# ControlPoint.net
KiCad netlist of a schematic drawn in Altium Designer
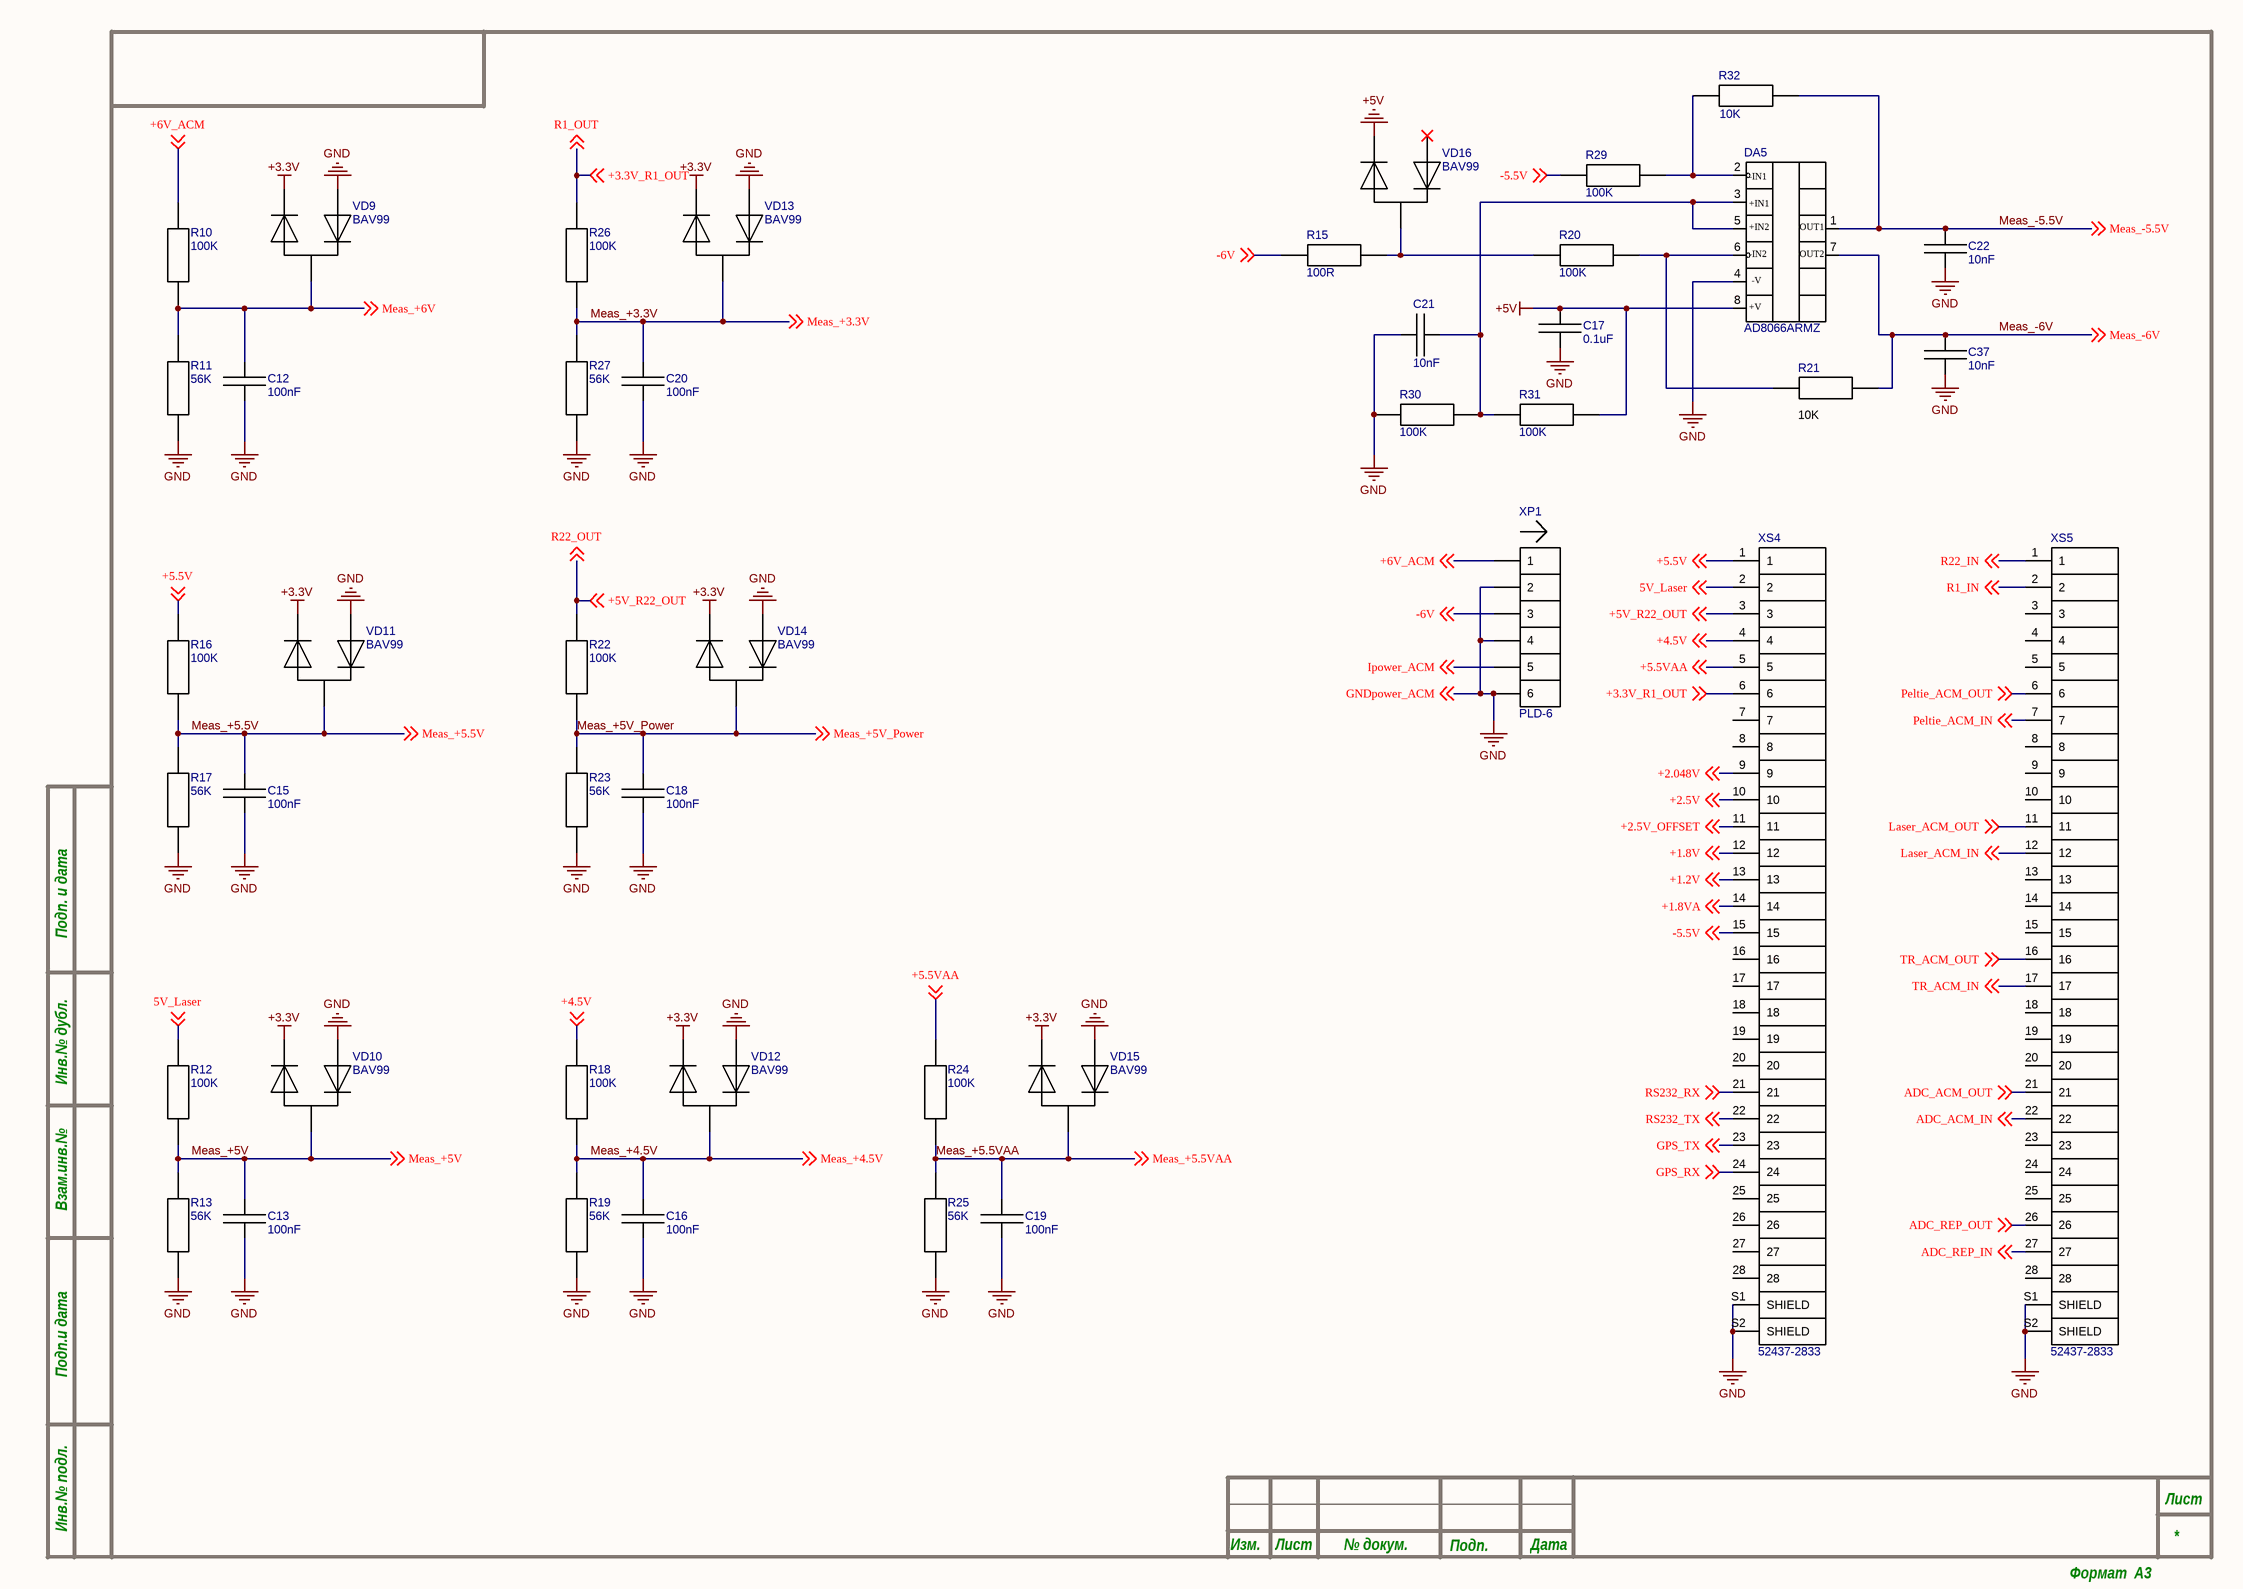
[diagram p0: ControlPoint.SchDoc]

(export (version "E")
  (design (tool "Eeschema 10.0.6"))
  (components
    (comp (ref "C12")
      (value "100nF")
      (footprint "0402C")
      (description "C0402-100nF 10% 50V")
      (fields
        (field (name "PART NUMBER") "SMD CAP CER 100nF ±10% 50V X5R 0402")
        (field (name "ADDED_BY") "Rutel@Mail.ru")
      )
      (libsource (lib "Test_Stand_Pergam") (part "C0402-100nF 10% 50V"))
    )
    (comp (ref "C13")
      (value "100nF")
      (footprint "0402C")
      (description "C0402-100nF 10% 50V")
      (fields
        (field (name "PART NUMBER") "SMD CAP CER 100nF ±10% 50V X5R 0402")
        (field (name "ADDED_BY") "Rutel@Mail.ru")
      )
      (libsource (lib "Test_Stand_Pergam") (part "C0402-100nF 10% 50V"))
    )
    (comp (ref "C15")
      (value "100nF")
      (footprint "0402C")
      (description "C0402-100nF 10% 50V")
      (fields
        (field (name "PART NUMBER") "SMD CAP CER 100nF ±10% 50V X5R 0402")
        (field (name "ADDED_BY") "Rutel@Mail.ru")
      )
      (libsource (lib "Test_Stand_Pergam") (part "C0402-100nF 10% 50V"))
    )
    (comp (ref "C16")
      (value "100nF")
      (footprint "0402C")
      (description "C0402-100nF 10% 50V")
      (fields
        (field (name "PART NUMBER") "SMD CAP CER 100nF ±10% 50V X5R 0402")
        (field (name "ADDED_BY") "Rutel@Mail.ru")
      )
      (libsource (lib "Test_Stand_Pergam") (part "C0402-100nF 10% 50V"))
    )
    (comp (ref "C17")
      (value "0.1uF")
      (footprint "0603C")
      (description "C0603 0.1UF 10% 50V")
      (fields
        (field (name "PART NUMBER") "SMD CAP CER 0.1UF ±10% 50V X7R 0603")
        (field (name "ADDED_BY") "anton@teslatec.ru")
      )
      (libsource (lib "Test_Stand_Pergam") (part "C0603-0.1UF 10% 50V"))
    )
    (comp (ref "C18")
      (value "100nF")
      (footprint "0402C")
      (description "C0402-100nF 10% 50V")
      (fields
        (field (name "PART NUMBER") "SMD CAP CER 100nF ±10% 50V X5R 0402")
        (field (name "ADDED_BY") "Rutel@Mail.ru")
      )
      (libsource (lib "Test_Stand_Pergam") (part "C0402-100nF 10% 50V"))
    )
    (comp (ref "C19")
      (value "100nF")
      (footprint "0402C")
      (description "C0402-100nF 10% 50V")
      (fields
        (field (name "PART NUMBER") "SMD CAP CER 100nF ±10% 50V X5R 0402")
        (field (name "ADDED_BY") "Rutel@Mail.ru")
      )
      (libsource (lib "Test_Stand_Pergam") (part "C0402-100nF 10% 50V"))
    )
    (comp (ref "C20")
      (value "100nF")
      (footprint "0402C")
      (description "C0402-100nF 10% 50V")
      (fields
        (field (name "PART NUMBER") "SMD CAP CER 100nF ±10% 50V X5R 0402")
        (field (name "ADDED_BY") "Rutel@Mail.ru")
      )
      (libsource (lib "Test_Stand_Pergam") (part "C0402-100nF 10% 50V"))
    )
    (comp (ref "C21")
      (value "10nF")
      (footprint "0402C")
      (description "C0402-10nF 10% 50V")
      (fields
        (field (name "PART NUMBER") "SMD CAP CER 10nF ±10% 50V X5R 0402")
        (field (name "ADDED_BY") "Rutel@Mail.ru")
      )
      (libsource (lib "Test_Stand_Pergam") (part "C0402-10nF 10% 50V"))
    )
    (comp (ref "C22")
      (value "10nF")
      (footprint "0402C")
      (description "C0402-10nF 10% 50V")
      (fields
        (field (name "PART NUMBER") "SMD CAP CER 10nF ±10% 50V X5R 0402")
        (field (name "ADDED_BY") "Rutel@Mail.ru")
      )
      (libsource (lib "Test_Stand_Pergam") (part "C0402-10nF 10% 50V"))
    )
    (comp (ref "C37")
      (value "10nF")
      (footprint "0402C")
      (description "C0402-10nF 10% 50V")
      (fields
        (field (name "PART NUMBER") "SMD CAP CER 10nF ±10% 50V X5R 0402")
        (field (name "ADDED_BY") "Rutel@Mail.ru")
      )
      (libsource (lib "Test_Stand_Pergam") (part "C0402-10nF 10% 50V"))
    )
    (comp (ref "DA5")
      (value "AD8066ARMZ")
      (footprint "MSOP-8")
      (description "High Performance, 145 MHz FastFET Op Amps")
      (fields (field (name "ADDED_BY") "irdolgopolowa@yandex.ru"))
      (libsource (lib "Test_Stand_Pergam") (part "AD8066ARMZ"))
    )
    (comp (ref "R10")
      (value "100K")
      (footprint "R0402")
      (description "Resistor SMD 100K 1% 0402")
      (fields
        (field (name "PART NUMBER") "SMD RES 100 KOHM 1% ±100ppm/°C 0402")
        (field (name "ADDED_BY") "Rutel@teslatec.ru")
      )
      (libsource (lib "Test_Stand_Pergam") (part "R0402-100K"))
    )
    (comp (ref "R11")
      (value "56K")
      (footprint "R0402")
      (description "Resistor SMD 56K 1% 0402")
      (fields
        (field (name "PART NUMBER") "SMD RES 56K KOHM 1% ±100ppm/°C 0402")
        (field (name "ADDED_BY") "ridel_av@teslatec.ru")
      )
      (libsource (lib "Test_Stand_Pergam") (part "R0402-56K"))
    )
    (comp (ref "R12")
      (value "100K")
      (footprint "R0402")
      (description "Resistor SMD 100K 1% 0402")
      (fields
        (field (name "PART NUMBER") "SMD RES 100 KOHM 1% ±100ppm/°C 0402")
        (field (name "ADDED_BY") "Rutel@teslatec.ru")
      )
      (libsource (lib "Test_Stand_Pergam") (part "R0402-100K"))
    )
    (comp (ref "R13")
      (value "56K")
      (footprint "R0402")
      (description "Resistor SMD 56K 1% 0402")
      (fields
        (field (name "PART NUMBER") "SMD RES 56K KOHM 1% ±100ppm/°C 0402")
        (field (name "ADDED_BY") "ridel_av@teslatec.ru")
      )
      (libsource (lib "Test_Stand_Pergam") (part "R0402-56K"))
    )
    (comp (ref "R15")
      (value "100R")
      (footprint "R0402")
      (description "Resistor SMD 100R 1% 0402")
      (fields
        (field (name "PART NUMBER") "SMD RES 100 OHM 1% ±100ppm/°C 0402")
        (field (name "ADDED_BY") "irdolgopolowa@yandex.ru")
      )
      (libsource (lib "Test_Stand_Pergam") (part "R0402-100R"))
    )
    (comp (ref "R16")
      (value "100K")
      (footprint "R0402")
      (description "Resistor SMD 100K 1% 0402")
      (fields
        (field (name "PART NUMBER") "SMD RES 100 KOHM 1% ±100ppm/°C 0402")
        (field (name "ADDED_BY") "Rutel@teslatec.ru")
      )
      (libsource (lib "Test_Stand_Pergam") (part "R0402-100K"))
    )
    (comp (ref "R17")
      (value "56K")
      (footprint "R0402")
      (description "Resistor SMD 56K 1% 0402")
      (fields
        (field (name "PART NUMBER") "SMD RES 56K KOHM 1% ±100ppm/°C 0402")
        (field (name "ADDED_BY") "ridel_av@teslatec.ru")
      )
      (libsource (lib "Test_Stand_Pergam") (part "R0402-56K"))
    )
    (comp (ref "R18")
      (value "100K")
      (footprint "R0402")
      (description "Resistor SMD 100K 1% 0402")
      (fields
        (field (name "PART NUMBER") "SMD RES 100 KOHM 1% ±100ppm/°C 0402")
        (field (name "ADDED_BY") "Rutel@teslatec.ru")
      )
      (libsource (lib "Test_Stand_Pergam") (part "R0402-100K"))
    )
    (comp (ref "R19")
      (value "56K")
      (footprint "R0402")
      (description "Resistor SMD 56K 1% 0402")
      (fields
        (field (name "PART NUMBER") "SMD RES 56K KOHM 1% ±100ppm/°C 0402")
        (field (name "ADDED_BY") "ridel_av@teslatec.ru")
      )
      (libsource (lib "Test_Stand_Pergam") (part "R0402-56K"))
    )
    (comp (ref "R20")
      (value "100K")
      (footprint "R0402")
      (description "Resistor SMD 100K 1% 0402")
      (fields
        (field (name "PART NUMBER") "SMD RES 100 KOHM 1% ±100ppm/°C 0402")
        (field (name "ADDED_BY") "Rutel@teslatec.ru")
      )
      (libsource (lib "Test_Stand_Pergam") (part "R0402-100K"))
    )
    (comp (ref "R21")
      (value "10K")
      (footprint "R0402")
      (description "Resistor SMD 10K 1% 0402")
      (fields
        (field (name "PART NUMBER") "SMD RES 10 KOHM 1% ±100ppm/°C 0402")
        (field (name "ADDED_BY") "Rutel@teslatec.ru")
      )
      (libsource (lib "Test_Stand_Pergam") (part "R0402-10K"))
    )
    (comp (ref "R22")
      (value "100K")
      (footprint "R0402")
      (description "Resistor SMD 100K 1% 0402")
      (fields
        (field (name "PART NUMBER") "SMD RES 100 KOHM 1% ±100ppm/°C 0402")
        (field (name "ADDED_BY") "Rutel@teslatec.ru")
      )
      (libsource (lib "Test_Stand_Pergam") (part "R0402-100K"))
    )
    (comp (ref "R23")
      (value "56K")
      (footprint "R0402")
      (description "Resistor SMD 56K 1% 0402")
      (fields
        (field (name "PART NUMBER") "SMD RES 56K KOHM 1% ±100ppm/°C 0402")
        (field (name "ADDED_BY") "ridel_av@teslatec.ru")
      )
      (libsource (lib "Test_Stand_Pergam") (part "R0402-56K"))
    )
    (comp (ref "R24")
      (value "100K")
      (footprint "R0402")
      (description "Resistor SMD 100K 1% 0402")
      (fields
        (field (name "PART NUMBER") "SMD RES 100 KOHM 1% ±100ppm/°C 0402")
        (field (name "ADDED_BY") "Rutel@teslatec.ru")
      )
      (libsource (lib "Test_Stand_Pergam") (part "R0402-100K"))
    )
    (comp (ref "R25")
      (value "56K")
      (footprint "R0402")
      (description "Resistor SMD 56K 1% 0402")
      (fields
        (field (name "PART NUMBER") "SMD RES 56K KOHM 1% ±100ppm/°C 0402")
        (field (name "ADDED_BY") "ridel_av@teslatec.ru")
      )
      (libsource (lib "Test_Stand_Pergam") (part "R0402-56K"))
    )
    (comp (ref "R26")
      (value "100K")
      (footprint "R0402")
      (description "Resistor SMD 100K 1% 0402")
      (fields
        (field (name "PART NUMBER") "SMD RES 100 KOHM 1% ±100ppm/°C 0402")
        (field (name "ADDED_BY") "Rutel@teslatec.ru")
      )
      (libsource (lib "Test_Stand_Pergam") (part "R0402-100K"))
    )
    (comp (ref "R27")
      (value "56K")
      (footprint "R0402")
      (description "Resistor SMD 56K 1% 0402")
      (fields
        (field (name "PART NUMBER") "SMD RES 56K KOHM 1% ±100ppm/°C 0402")
        (field (name "ADDED_BY") "ridel_av@teslatec.ru")
      )
      (libsource (lib "Test_Stand_Pergam") (part "R0402-56K"))
    )
    (comp (ref "R29")
      (value "100K")
      (footprint "R0402")
      (description "Resistor SMD 100K 1% 0402")
      (fields
        (field (name "PART NUMBER") "SMD RES 100 KOHM 1% ±100ppm/°C 0402")
        (field (name "ADDED_BY") "Rutel@teslatec.ru")
      )
      (libsource (lib "Test_Stand_Pergam") (part "R0402-100K"))
    )
    (comp (ref "R30")
      (value "100K")
      (footprint "R0402")
      (description "Resistor SMD 100K 1% 0402")
      (fields
        (field (name "PART NUMBER") "SMD RES 100 KOHM 1% ±100ppm/°C 0402")
        (field (name "ADDED_BY") "Rutel@teslatec.ru")
      )
      (libsource (lib "Test_Stand_Pergam") (part "R0402-100K"))
    )
    (comp (ref "R31")
      (value "100K")
      (footprint "R0402")
      (description "Resistor SMD 100K 1% 0402")
      (fields
        (field (name "PART NUMBER") "SMD RES 100 KOHM 1% ±100ppm/°C 0402")
        (field (name "ADDED_BY") "Rutel@teslatec.ru")
      )
      (libsource (lib "Test_Stand_Pergam") (part "R0402-100K"))
    )
    (comp (ref "R32")
      (value "10K")
      (footprint "R0402")
      (description "Resistor SMD 10K 1% 0402")
      (fields
        (field (name "PART NUMBER") "SMD RES 10 KOHM 1% ±100ppm/°C 0402")
        (field (name "ADDED_BY") "Rutel@teslatec.ru")
      )
      (libsource (lib "Test_Stand_Pergam") (part "R0402-10K"))
    )
    (comp (ref "VD9")
      (value "BAV99")
      (footprint "SOT-23-3")
      (description "BAV99, UMW, 70В, 200мА")
      (fields (field (name "ADDED_BY") "andrew@teslatec.ru"))
      (libsource (lib "Test_Stand_Pergam") (part "BAV99"))
    )
    (comp (ref "VD10")
      (value "BAV99")
      (footprint "SOT-23-3")
      (description "BAV99, UMW, 70В, 200мА")
      (fields (field (name "ADDED_BY") "andrew@teslatec.ru"))
      (libsource (lib "Test_Stand_Pergam") (part "BAV99"))
    )
    (comp (ref "VD11")
      (value "BAV99")
      (footprint "SOT-23-3")
      (description "BAV99, UMW, 70В, 200мА")
      (fields (field (name "ADDED_BY") "andrew@teslatec.ru"))
      (libsource (lib "Test_Stand_Pergam") (part "BAV99"))
    )
    (comp (ref "VD12")
      (value "BAV99")
      (footprint "SOT-23-3")
      (description "BAV99, UMW, 70В, 200мА")
      (fields (field (name "ADDED_BY") "andrew@teslatec.ru"))
      (libsource (lib "Test_Stand_Pergam") (part "BAV99"))
    )
    (comp (ref "VD13")
      (value "BAV99")
      (footprint "SOT-23-3")
      (description "BAV99, UMW, 70В, 200мА")
      (fields (field (name "ADDED_BY") "andrew@teslatec.ru"))
      (libsource (lib "Test_Stand_Pergam") (part "BAV99"))
    )
    (comp (ref "VD14")
      (value "BAV99")
      (footprint "SOT-23-3")
      (description "BAV99, UMW, 70В, 200мА")
      (fields (field (name "ADDED_BY") "andrew@teslatec.ru"))
      (libsource (lib "Test_Stand_Pergam") (part "BAV99"))
    )
    (comp (ref "VD15")
      (value "BAV99")
      (footprint "SOT-23-3")
      (description "BAV99, UMW, 70В, 200мА")
      (fields (field (name "ADDED_BY") "andrew@teslatec.ru"))
      (libsource (lib "Test_Stand_Pergam") (part "BAV99"))
    )
    (comp (ref "VD16")
      (value "BAV99")
      (footprint "SOT-23-3")
      (description "BAV99, UMW, 70В, 200мА")
      (fields (field (name "ADDED_BY") "andrew@teslatec.ru"))
      (libsource (lib "Test_Stand_Pergam") (part "BAV99"))
    )
    (comp (ref "XP1")
      (value "PLD-6")
      (footprint "PLD-6")
      (description "Pin Header Pitch 2.54mm")
      (fields
        (field (name "PART NUMBER") "PLD-6 (DS1021-2x3)")
        (field (name "ADDED_BY") "ponomarev_ke@teslatec.ru")
      )
      (libsource (lib "Test_Stand_Pergam") (part "PLD-6"))
    )
    (comp (ref "XS4")
      (value "52437-2833")
      (footprint "MOLEX_52437-2833")
      (description "28 Position FFC, FPC Connector Contacts, Bottom 0.020 _0.50mm_ Surface Mount, Right Angle")
      (fields
        (field (name "PART NUMBER") "52437-2833 (MOLEX)")
        (field (name "MATING PART") "FFCA 28pin, 0.5mm pitch, AVM 20624 80C 60V VW-1")
        (field (name "ADDED_BY") "ridel_av@teslatec.ru")
      )
      (libsource (lib "Test_Stand_Pergam") (part "52437-2833"))
    )
    (comp (ref "XS5")
      (value "52437-2833")
      (footprint "MOLEX_52437-2833")
      (description "28 Position FFC, FPC Connector Contacts, Bottom 0.020 _0.50mm_ Surface Mount, Right Angle")
      (fields
        (field (name "PART NUMBER") "52437-2833 (MOLEX)")
        (field (name "MATING PART") "FFCA 28pin, 0.5mm pitch, AVM 20624 80C 60V VW-1")
        (field (name "ADDED_BY") "ridel_av@teslatec.ru")
      )
      (libsource (lib "Test_Stand_Pergam") (part "52437-2833"))
    )
  )
  (nets
    (net (code "1") (name "+1.2V") (class "Default")
      (node (ref "XS4") (pin "13") (pinfunction "13_13") (pintype "passive"))
    )
    (net (code "2") (name "+1.8V") (class "Default")
      (node (ref "XS4") (pin "12") (pinfunction "12_12") (pintype "passive"))
    )
    (net (code "3") (name "+1.8VA") (class "Default")
      (node (ref "XS4") (pin "14") (pinfunction "14_14") (pintype "passive"))
    )
    (net (code "4") (name "+2.5V") (class "Default")
      (node (ref "XS4") (pin "10") (pinfunction "10_10") (pintype "passive"))
    )
    (net (code "5") (name "+2.5V_OFFSET") (class "Default")
      (node (ref "XS4") (pin "11") (pinfunction "11_11") (pintype "passive"))
    )
    (net (code "6") (name "+2.048V") (class "Default")
      (node (ref "XS4") (pin "9") (pinfunction "9_9") (pintype "passive"))
    )
    (net (code "7") (name "+3.3V") (class "Default")
      (node (ref "VD10") (pin "2") (pinfunction "2_2") (pintype "passive"))
      (node (ref "VD11") (pin "2") (pinfunction "2_2") (pintype "passive"))
      (node (ref "VD12") (pin "2") (pinfunction "2_2") (pintype "passive"))
      (node (ref "VD13") (pin "2") (pinfunction "2_2") (pintype "passive"))
      (node (ref "VD14") (pin "2") (pinfunction "2_2") (pintype "passive"))
      (node (ref "VD15") (pin "2") (pinfunction "2_2") (pintype "passive"))
      (node (ref "VD9") (pin "2") (pinfunction "2_2") (pintype "passive"))
    )
    (net (code "8") (name "+3.3V_R1_OUT") (class "Default")
      (node (ref "R26") (pin "1") (pinfunction "1_1") (pintype "passive"))
      (node (ref "XS4") (pin "6") (pinfunction "6_6") (pintype "passive"))
    )
    (net (code "9") (name "+4.5V") (class "Default")
      (node (ref "R18") (pin "1") (pinfunction "1_1") (pintype "passive"))
      (node (ref "XS4") (pin "4") (pinfunction "4_4") (pintype "passive"))
    )
    (net (code "10") (name "+5.5V") (class "Default")
      (node (ref "R16") (pin "1") (pinfunction "1_1") (pintype "passive"))
      (node (ref "XS4") (pin "1") (pinfunction "1_1") (pintype "passive"))
    )
    (net (code "11") (name "+5.5VAA") (class "Default")
      (node (ref "R24") (pin "1") (pinfunction "1_1") (pintype "passive"))
      (node (ref "XS4") (pin "5") (pinfunction "5_5") (pintype "passive"))
    )
    (net (code "12") (name "+5V") (class "Default")
      (node (ref "C17") (pin "1") (pinfunction "1_1") (pintype "passive"))
      (node (ref "DA5") (pin "8") (pinfunction "+VS_8") (pintype "passive"))
      (node (ref "R31") (pin "2") (pinfunction "2_2") (pintype "passive"))
      (node (ref "VD16") (pin "2") (pinfunction "2_2") (pintype "passive"))
    )
    (net (code "13") (name "+5V_R22_OUT") (class "Default")
      (node (ref "R22") (pin "1") (pinfunction "1_1") (pintype "passive"))
      (node (ref "XS4") (pin "3") (pinfunction "3_3") (pintype "passive"))
    )
    (net (code "14") (name "+6V_ACM") (class "Default")
      (node (ref "R10") (pin "1") (pinfunction "1_1") (pintype "passive"))
      (node (ref "XP1") (pin "1") (pinfunction "1_1") (pintype "passive"))
    )
    (net (code "15") (name "-5.5V") (class "Default")
      (node (ref "R29") (pin "1") (pinfunction "1_1") (pintype "passive"))
      (node (ref "XS4") (pin "15") (pinfunction "15_15") (pintype "passive"))
    )
    (net (code "16") (name "-6V") (class "Default")
      (node (ref "R15") (pin "1") (pinfunction "1_1") (pintype "passive"))
      (node (ref "XP1") (pin "3") (pinfunction "3_3") (pintype "passive"))
    )
    (net (code "17") (name "5V_Laser") (class "Default")
      (node (ref "R12") (pin "1") (pinfunction "1_1") (pintype "passive"))
      (node (ref "XS4") (pin "2") (pinfunction "2_2") (pintype "passive"))
    )
    (net (code "18") (name "ADC_ACM_IN") (class "Default")
      (node (ref "XS5") (pin "22") (pinfunction "22_22") (pintype "passive"))
    )
    (net (code "19") (name "ADC_ACM_OUT") (class "Default")
      (node (ref "XS5") (pin "21") (pinfunction "21_21") (pintype "passive"))
    )
    (net (code "20") (name "ADC_REP_IN") (class "Default")
      (node (ref "XS5") (pin "27") (pinfunction "27_27") (pintype "passive"))
    )
    (net (code "21") (name "ADC_REP_OUT") (class "Default")
      (node (ref "XS5") (pin "26") (pinfunction "26_26") (pintype "passive"))
    )
    (net (code "22") (name "GND") (class "Default")
      (node (ref "C12") (pin "1") (pinfunction "1_1") (pintype "passive"))
      (node (ref "C13") (pin "1") (pinfunction "1_1") (pintype "passive"))
      (node (ref "C15") (pin "1") (pinfunction "1_1") (pintype "passive"))
      (node (ref "C16") (pin "1") (pinfunction "1_1") (pintype "passive"))
      (node (ref "C17") (pin "2") (pinfunction "2_2") (pintype "passive"))
      (node (ref "C18") (pin "1") (pinfunction "1_1") (pintype "passive"))
      (node (ref "C19") (pin "1") (pinfunction "1_1") (pintype "passive"))
      (node (ref "C20") (pin "1") (pinfunction "1_1") (pintype "passive"))
      (node (ref "C21") (pin "1") (pinfunction "1_1") (pintype "passive"))
      (node (ref "C22") (pin "1") (pinfunction "1_1") (pintype "passive"))
      (node (ref "C37") (pin "1") (pinfunction "1_1") (pintype "passive"))
      (node (ref "DA5") (pin "4") (pinfunction "-VS_4") (pintype "passive"))
      (node (ref "R11") (pin "2") (pinfunction "2_2") (pintype "passive"))
      (node (ref "R13") (pin "2") (pinfunction "2_2") (pintype "passive"))
      (node (ref "R17") (pin "2") (pinfunction "2_2") (pintype "passive"))
      (node (ref "R19") (pin "2") (pinfunction "2_2") (pintype "passive"))
      (node (ref "R23") (pin "2") (pinfunction "2_2") (pintype "passive"))
      (node (ref "R25") (pin "2") (pinfunction "2_2") (pintype "passive"))
      (node (ref "R27") (pin "2") (pinfunction "2_2") (pintype "passive"))
      (node (ref "R30") (pin "1") (pinfunction "1_1") (pintype "passive"))
      (node (ref "VD10") (pin "1") (pinfunction "1_1") (pintype "passive"))
      (node (ref "VD11") (pin "1") (pinfunction "1_1") (pintype "passive"))
      (node (ref "VD12") (pin "1") (pinfunction "1_1") (pintype "passive"))
      (node (ref "VD13") (pin "1") (pinfunction "1_1") (pintype "passive"))
      (node (ref "VD14") (pin "1") (pinfunction "1_1") (pintype "passive"))
      (node (ref "VD15") (pin "1") (pinfunction "1_1") (pintype "passive"))
      (node (ref "VD9") (pin "1") (pinfunction "1_1") (pintype "passive"))
      (node (ref "XP1") (pin "2") (pinfunction "2_2") (pintype "passive"))
      (node (ref "XP1") (pin "4") (pinfunction "4_4") (pintype "passive"))
      (node (ref "XP1") (pin "6") (pinfunction "6_6") (pintype "passive"))
      (node (ref "XS4") (pin "S1") (pinfunction "SHIELD_S1") (pintype "passive"))
      (node (ref "XS4") (pin "S2") (pinfunction "SHIELD_S2") (pintype "passive"))
      (node (ref "XS5") (pin "S1") (pinfunction "SHIELD_S1") (pintype "passive"))
      (node (ref "XS5") (pin "S2") (pinfunction "SHIELD_S2") (pintype "passive"))
    )
    (net (code "23") (name "GPS_RX") (class "Default")
      (node (ref "XS4") (pin "24") (pinfunction "24_24") (pintype "passive"))
    )
    (net (code "24") (name "GPS_TX") (class "Default")
      (node (ref "XS4") (pin "23") (pinfunction "23_23") (pintype "passive"))
    )
    (net (code "25") (name "Ipower_ACM") (class "Default")
      (node (ref "XP1") (pin "5") (pinfunction "5_5") (pintype "passive"))
    )
    (net (code "26") (name "Laser_ACM_IN") (class "Default")
      (node (ref "XS5") (pin "12") (pinfunction "12_12") (pintype "passive"))
    )
    (net (code "27") (name "Laser_ACM_OUT") (class "Default")
      (node (ref "XS5") (pin "11") (pinfunction "11_11") (pintype "passive"))
    )
    (net (code "28") (name "Meas_+3.3V") (class "Default")
      (node (ref "C20") (pin "2") (pinfunction "2_2") (pintype "passive"))
      (node (ref "R26") (pin "2") (pinfunction "2_2") (pintype "passive"))
      (node (ref "R27") (pin "1") (pinfunction "1_1") (pintype "passive"))
      (node (ref "VD13") (pin "3") (pinfunction "3_3") (pintype "passive"))
    )
    (net (code "29") (name "Meas_+4.5V") (class "Default")
      (node (ref "C16") (pin "2") (pinfunction "2_2") (pintype "passive"))
      (node (ref "R18") (pin "2") (pinfunction "2_2") (pintype "passive"))
      (node (ref "R19") (pin "1") (pinfunction "1_1") (pintype "passive"))
      (node (ref "VD12") (pin "3") (pinfunction "3_3") (pintype "passive"))
    )
    (net (code "30") (name "Meas_+5.5V") (class "Default")
      (node (ref "C15") (pin "2") (pinfunction "2_2") (pintype "passive"))
      (node (ref "R16") (pin "2") (pinfunction "2_2") (pintype "passive"))
      (node (ref "R17") (pin "1") (pinfunction "1_1") (pintype "passive"))
      (node (ref "VD11") (pin "3") (pinfunction "3_3") (pintype "passive"))
    )
    (net (code "31") (name "Meas_+5.5VAA") (class "Default")
      (node (ref "C19") (pin "2") (pinfunction "2_2") (pintype "passive"))
      (node (ref "R24") (pin "2") (pinfunction "2_2") (pintype "passive"))
      (node (ref "R25") (pin "1") (pinfunction "1_1") (pintype "passive"))
      (node (ref "VD15") (pin "3") (pinfunction "3_3") (pintype "passive"))
    )
    (net (code "32") (name "Meas_+5V") (class "Default")
      (node (ref "C13") (pin "2") (pinfunction "2_2") (pintype "passive"))
      (node (ref "R12") (pin "2") (pinfunction "2_2") (pintype "passive"))
      (node (ref "R13") (pin "1") (pinfunction "1_1") (pintype "passive"))
      (node (ref "VD10") (pin "3") (pinfunction "3_3") (pintype "passive"))
    )
    (net (code "33") (name "Meas_+5V_Power") (class "Default")
      (node (ref "C18") (pin "2") (pinfunction "2_2") (pintype "passive"))
      (node (ref "R22") (pin "2") (pinfunction "2_2") (pintype "passive"))
      (node (ref "R23") (pin "1") (pinfunction "1_1") (pintype "passive"))
      (node (ref "VD14") (pin "3") (pinfunction "3_3") (pintype "passive"))
    )
    (net (code "34") (name "Meas_+6V") (class "Default")
      (node (ref "C12") (pin "2") (pinfunction "2_2") (pintype "passive"))
      (node (ref "R10") (pin "2") (pinfunction "2_2") (pintype "passive"))
      (node (ref "R11") (pin "1") (pinfunction "1_1") (pintype "passive"))
      (node (ref "VD9") (pin "3") (pinfunction "3_3") (pintype "passive"))
    )
    (net (code "35") (name "Meas_-5.5V") (class "Default")
      (node (ref "C22") (pin "2") (pinfunction "2_2") (pintype "passive"))
      (node (ref "DA5") (pin "1") (pinfunction "VOUT_1") (pintype "passive"))
      (node (ref "R32") (pin "2") (pinfunction "2_2") (pintype "passive"))
    )
    (net (code "36") (name "Meas_-6V") (class "Default")
      (node (ref "C37") (pin "2") (pinfunction "2_2") (pintype "passive"))
      (node (ref "DA5") (pin "7") (pinfunction "VOUT2_7") (pintype "passive"))
      (node (ref "R21") (pin "2") (pinfunction "2_2") (pintype "passive"))
    )
    (net (code "37") (name "Net-(DA5-+IN1)") (class "Default")
      (node (ref "C21") (pin "2") (pinfunction "2_2") (pintype "passive"))
      (node (ref "DA5") (pin "3") (pinfunction "+IN1_3") (pintype "passive"))
      (node (ref "DA5") (pin "5") (pinfunction "+IN2_5") (pintype "passive"))
      (node (ref "R30") (pin "2") (pinfunction "2_2") (pintype "passive"))
      (node (ref "R31") (pin "1") (pinfunction "1_1") (pintype "passive"))
    )
    (net (code "38") (name "Net-(DA5--IN1)") (class "Default")
      (node (ref "DA5") (pin "2") (pinfunction "-IN1_2") (pintype "passive"))
      (node (ref "R29") (pin "2") (pinfunction "2_2") (pintype "passive"))
      (node (ref "R32") (pin "1") (pinfunction "1_1") (pintype "passive"))
    )
    (net (code "39") (name "Net-(DA5--IN2)") (class "Default")
      (node (ref "DA5") (pin "6") (pinfunction "-IN2_6") (pintype "passive"))
      (node (ref "R20") (pin "2") (pinfunction "2_2") (pintype "passive"))
      (node (ref "R21") (pin "1") (pinfunction "1_1") (pintype "passive"))
    )
    (net (code "40") (name "Net-(R15-Pad2)") (class "Default")
      (node (ref "R15") (pin "2") (pinfunction "2_2") (pintype "passive"))
      (node (ref "R20") (pin "1") (pinfunction "1_1") (pintype "passive"))
      (node (ref "VD16") (pin "3") (pinfunction "3_3") (pintype "passive"))
    )
    (net (code "41") (name "Peltie_ACM_IN") (class "Default")
      (node (ref "XS5") (pin "7") (pinfunction "7_7") (pintype "passive"))
    )
    (net (code "42") (name "Peltie_ACM_OUT") (class "Default")
      (node (ref "XS5") (pin "6") (pinfunction "6_6") (pintype "passive"))
    )
    (net (code "43") (name "R1_IN") (class "Default")
      (node (ref "XS5") (pin "2") (pinfunction "2_2") (pintype "passive"))
    )
    (net (code "44") (name "R22_IN") (class "Default")
      (node (ref "XS5") (pin "1") (pinfunction "1_1") (pintype "passive"))
    )
    (net (code "45") (name "RS232_RX") (class "Default")
      (node (ref "XS4") (pin "21") (pinfunction "21_21") (pintype "passive"))
    )
    (net (code "46") (name "RS232_TX") (class "Default")
      (node (ref "XS4") (pin "22") (pinfunction "22_22") (pintype "passive"))
    )
    (net (code "47") (name "TR_ACM_IN") (class "Default")
      (node (ref "XS5") (pin "17") (pinfunction "17_17") (pintype "passive"))
    )
    (net (code "48") (name "TR_ACM_OUT") (class "Default")
      (node (ref "XS5") (pin "16") (pinfunction "16_16") (pintype "passive"))
    )
    (net (code "49") (name "unconnected-(VD16-Pad1)") (class "Default")
      (node (ref "VD16") (pin "1") (pinfunction "1_1") (pintype "passive+no_connect"))
    )
    (net (code "50") (name "unconnected-(XS4-Pad7)") (class "Default")
      (node (ref "XS4") (pin "7") (pinfunction "7_7") (pintype "passive"))
    )
    (net (code "51") (name "unconnected-(XS4-Pad8)") (class "Default")
      (node (ref "XS4") (pin "8") (pinfunction "8_8") (pintype "passive"))
    )
    (net (code "52") (name "unconnected-(XS4-Pad16)") (class "Default")
      (node (ref "XS4") (pin "16") (pinfunction "16_16") (pintype "passive"))
    )
    (net (code "53") (name "unconnected-(XS4-Pad17)") (class "Default")
      (node (ref "XS4") (pin "17") (pinfunction "17_17") (pintype "passive"))
    )
    (net (code "54") (name "unconnected-(XS4-Pad18)") (class "Default")
      (node (ref "XS4") (pin "18") (pinfunction "18_18") (pintype "passive"))
    )
    (net (code "55") (name "unconnected-(XS4-Pad19)") (class "Default")
      (node (ref "XS4") (pin "19") (pinfunction "19_19") (pintype "passive"))
    )
    (net (code "56") (name "unconnected-(XS4-Pad20)") (class "Default")
      (node (ref "XS4") (pin "20") (pinfunction "20_20") (pintype "passive"))
    )
    (net (code "57") (name "unconnected-(XS4-Pad25)") (class "Default")
      (node (ref "XS4") (pin "25") (pinfunction "25_25") (pintype "passive"))
    )
    (net (code "58") (name "unconnected-(XS4-Pad26)") (class "Default")
      (node (ref "XS4") (pin "26") (pinfunction "26_26") (pintype "passive"))
    )
    (net (code "59") (name "unconnected-(XS4-Pad27)") (class "Default")
      (node (ref "XS4") (pin "27") (pinfunction "27_27") (pintype "passive"))
    )
    (net (code "60") (name "unconnected-(XS4-Pad28)") (class "Default")
      (node (ref "XS4") (pin "28") (pinfunction "28_28") (pintype "passive"))
    )
    (net (code "61") (name "unconnected-(XS5-Pad3)") (class "Default")
      (node (ref "XS5") (pin "3") (pinfunction "3_3") (pintype "passive"))
    )
    (net (code "62") (name "unconnected-(XS5-Pad4)") (class "Default")
      (node (ref "XS5") (pin "4") (pinfunction "4_4") (pintype "passive"))
    )
    (net (code "63") (name "unconnected-(XS5-Pad5)") (class "Default")
      (node (ref "XS5") (pin "5") (pinfunction "5_5") (pintype "passive"))
    )
    (net (code "64") (name "unconnected-(XS5-Pad8)") (class "Default")
      (node (ref "XS5") (pin "8") (pinfunction "8_8") (pintype "passive"))
    )
    (net (code "65") (name "unconnected-(XS5-Pad9)") (class "Default")
      (node (ref "XS5") (pin "9") (pinfunction "9_9") (pintype "passive"))
    )
    (net (code "66") (name "unconnected-(XS5-Pad10)") (class "Default")
      (node (ref "XS5") (pin "10") (pinfunction "10_10") (pintype "passive"))
    )
    (net (code "67") (name "unconnected-(XS5-Pad13)") (class "Default")
      (node (ref "XS5") (pin "13") (pinfunction "13_13") (pintype "passive"))
    )
    (net (code "68") (name "unconnected-(XS5-Pad14)") (class "Default")
      (node (ref "XS5") (pin "14") (pinfunction "14_14") (pintype "passive"))
    )
    (net (code "69") (name "unconnected-(XS5-Pad15)") (class "Default")
      (node (ref "XS5") (pin "15") (pinfunction "15_15") (pintype "passive"))
    )
    (net (code "70") (name "unconnected-(XS5-Pad18)") (class "Default")
      (node (ref "XS5") (pin "18") (pinfunction "18_18") (pintype "passive"))
    )
    (net (code "71") (name "unconnected-(XS5-Pad19)") (class "Default")
      (node (ref "XS5") (pin "19") (pinfunction "19_19") (pintype "passive"))
    )
    (net (code "72") (name "unconnected-(XS5-Pad20)") (class "Default")
      (node (ref "XS5") (pin "20") (pinfunction "20_20") (pintype "passive"))
    )
    (net (code "73") (name "unconnected-(XS5-Pad23)") (class "Default")
      (node (ref "XS5") (pin "23") (pinfunction "23_23") (pintype "passive"))
    )
    (net (code "74") (name "unconnected-(XS5-Pad24)") (class "Default")
      (node (ref "XS5") (pin "24") (pinfunction "24_24") (pintype "passive"))
    )
    (net (code "75") (name "unconnected-(XS5-Pad25)") (class "Default")
      (node (ref "XS5") (pin "25") (pinfunction "25_25") (pintype "passive"))
    )
    (net (code "76") (name "unconnected-(XS5-Pad28)") (class "Default")
      (node (ref "XS5") (pin "28") (pinfunction "28_28") (pintype "passive"))
    )
  )
)
